# BigTimeTop.net
KiCad netlist of a schematic drawn in EAGLE
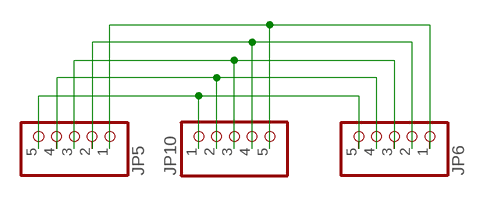
[diagram p0: schematic, sheet 1]

(export (version "E")
  (design (tool "Eeschema 10.0.6"))
  (components
    (comp (ref "JP5")
      (value "HEADER-1X576MIL")
      (footprint "eagle-import:1X05_ROUND_76")
      (libsource (lib "eagle-import") (part "HEADER-1X576MIL"))
    )
    (comp (ref "JP6")
      (value "HEADER-1X576MIL")
      (footprint "eagle-import:1X05_ROUND_76")
      (libsource (lib "eagle-import") (part "HEADER-1X576MIL"))
    )
    (comp (ref "JP10")
      (value "HEADER-1X576MIL")
      (footprint "eagle-import:1X05_ROUND_76")
      (libsource (lib "eagle-import") (part "HEADER-1X576MIL"))
    )
  )
  (nets
    (net (code "1") (name "Net-(JP10-Pad1)") (class "Default")
      (node (ref "JP10") (pin "1") (pinfunction "1_1") (pintype "passive"))
      (node (ref "JP5") (pin "5") (pinfunction "5_5") (pintype "passive"))
      (node (ref "JP6") (pin "5") (pinfunction "5_5") (pintype "passive"))
    )
    (net (code "2") (name "Net-(JP10-Pad2)") (class "Default")
      (node (ref "JP10") (pin "2") (pinfunction "2_2") (pintype "passive"))
      (node (ref "JP5") (pin "4") (pinfunction "4_4") (pintype "passive"))
      (node (ref "JP6") (pin "4") (pinfunction "4_4") (pintype "passive"))
    )
    (net (code "3") (name "Net-(JP10-Pad3)") (class "Default")
      (node (ref "JP10") (pin "3") (pinfunction "3_3") (pintype "passive"))
      (node (ref "JP5") (pin "3") (pinfunction "3_3") (pintype "passive"))
      (node (ref "JP6") (pin "3") (pinfunction "3_3") (pintype "passive"))
    )
    (net (code "4") (name "Net-(JP10-Pad4)") (class "Default")
      (node (ref "JP10") (pin "4") (pinfunction "4_4") (pintype "passive"))
      (node (ref "JP5") (pin "2") (pinfunction "2_2") (pintype "passive"))
      (node (ref "JP6") (pin "2") (pinfunction "2_2") (pintype "passive"))
    )
    (net (code "5") (name "Net-(JP10-Pad5)") (class "Default")
      (node (ref "JP10") (pin "5") (pinfunction "5_5") (pintype "passive"))
      (node (ref "JP5") (pin "1") (pinfunction "1_1") (pintype "passive"))
      (node (ref "JP6") (pin "1") (pinfunction "1_1") (pintype "passive"))
    )
  )
)
